# Thermocouple.net
KiCad netlist of a schematic drawn in EAGLE
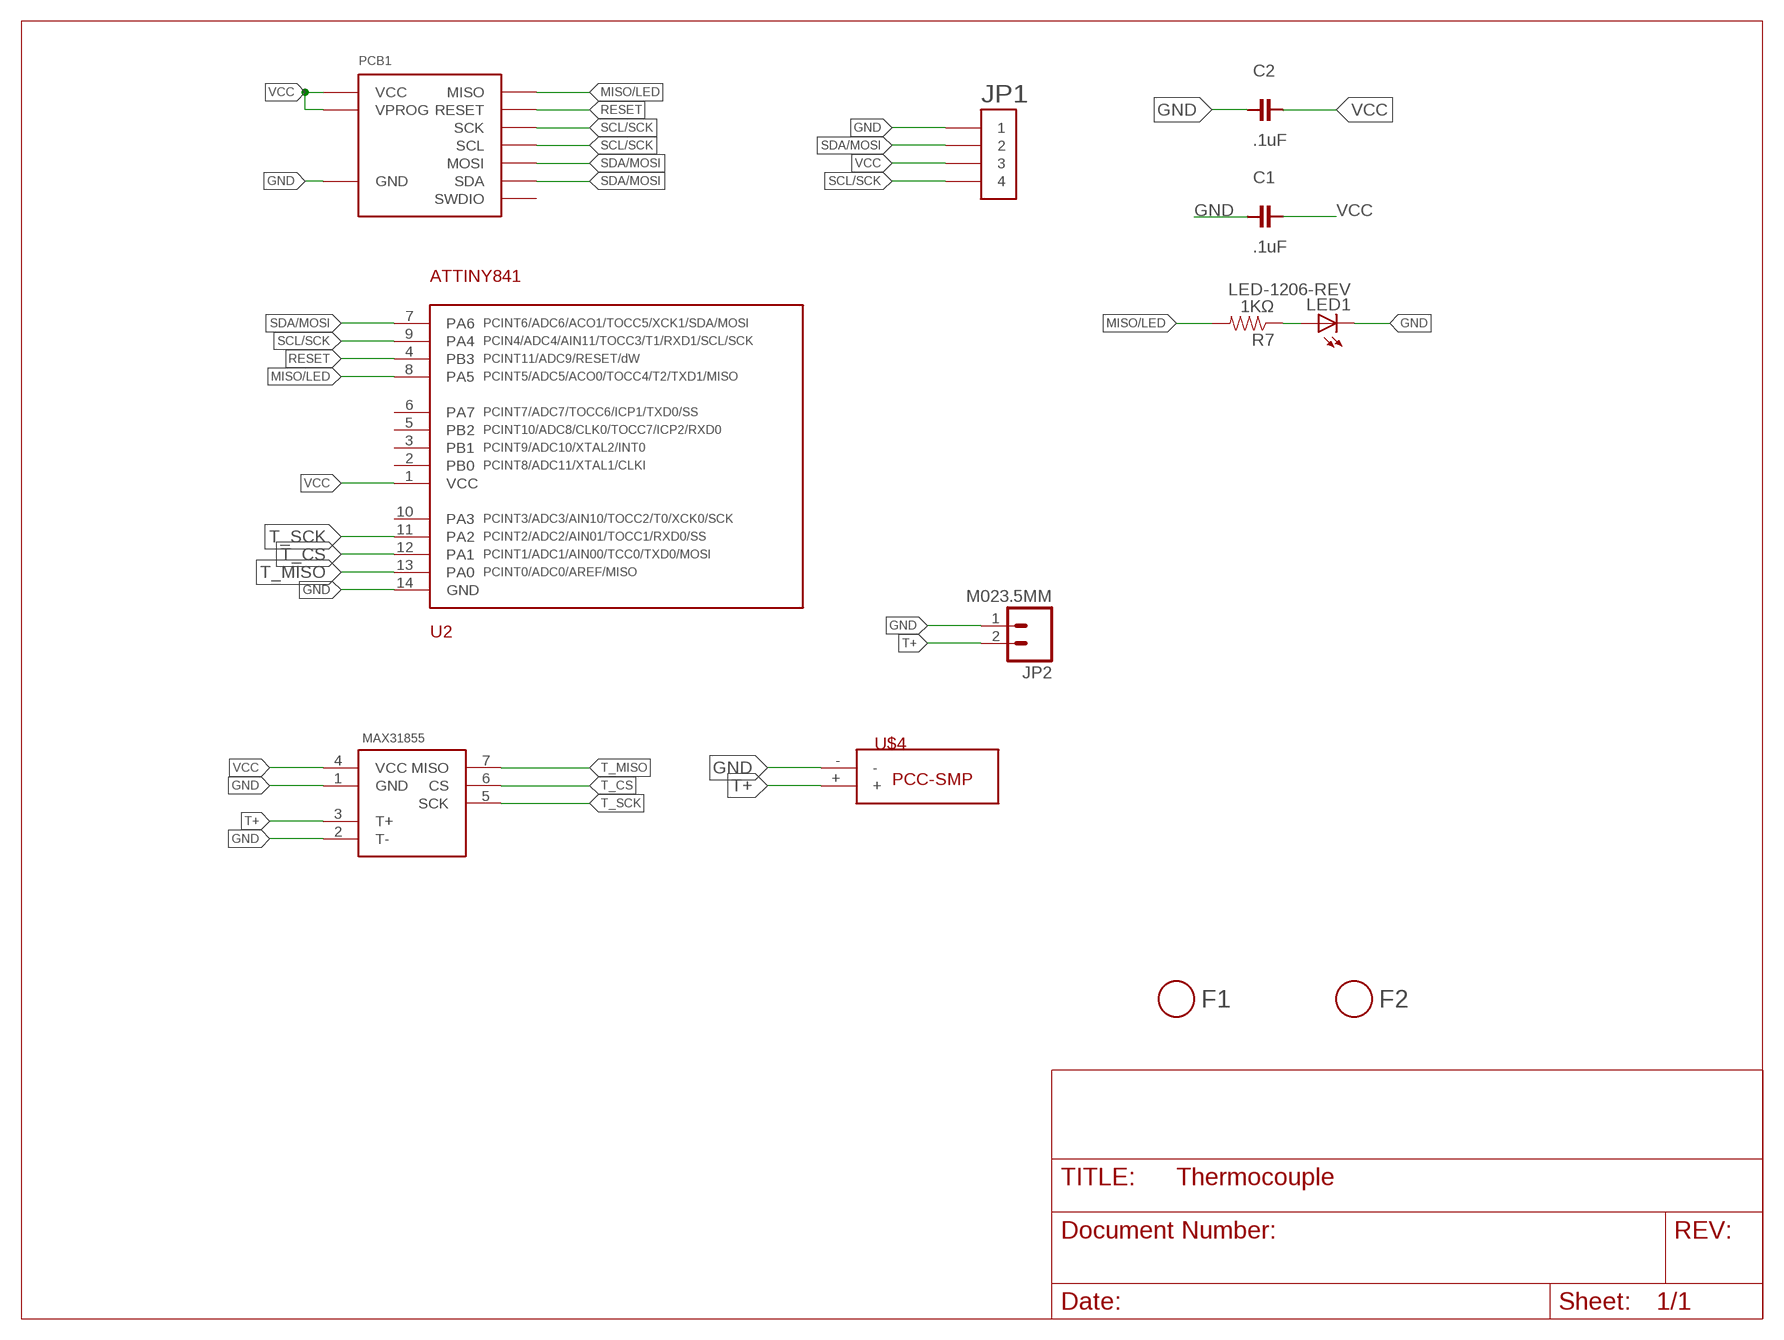
[diagram p0: schematic, sheet 1]

(export (version "E")
  (design (tool "Eeschema 10.0.6"))
  (components
    (comp (ref "C1")
      (value ".1uF")
      (footprint "eagle-import:0603")
      (fields (field (name "PARTNUM") "C0603C104K5RACTU"))
      (libsource (lib "eagle-import") (part "CAPACITOR-.1UF"))
    )
    (comp (ref "C2")
      (value ".1uF")
      (footprint "eagle-import:0603")
      (fields (field (name "PARTNUM") "C0603C104K5RACTU"))
      (libsource (lib "eagle-import") (part "CAPACITOR-.1UF"))
    )
    (comp (ref "F1")
      (value "FIDUCIAL")
      (footprint "eagle-import:FIDUCIAL_1MM")
      (libsource (lib "eagle-import") (part "FIDUCIAL"))
    )
    (comp (ref "F2")
      (value "FIDUCIAL")
      (footprint "eagle-import:FIDUCIAL_1MM")
      (libsource (lib "eagle-import") (part "FIDUCIAL"))
    )
    (comp (ref "JP1")
      (value "HEADER-1X4-AMPMODU")
      (footprint "eagle-import:AMPMODU-4P")
      (fields (field (name "PARTNUM") "147721-3"))
      (libsource (lib "eagle-import") (part "HEADER-1X4-AMPMODU"))
    )
    (comp (ref "JP2")
      (value "M023.5MM")
      (footprint "eagle-import:SCREWTERMINAL-3.5MM-2")
      (libsource (lib "eagle-import") (part "M023.5MM"))
    )
    (comp (ref "LED1")
      (value "LED-1206-REV")
      (footprint "eagle-import:LED-1206-REV")
      (fields (field (name "PARTNUM") "LTST-C230TBKT"))
      (libsource (lib "eagle-import") (part "LED-1206-REV"))
    )
    (comp (ref "PCB1")
      (value "DEVICE-PCB")
      (footprint "eagle-import:DEVICE-PCB")
      (fields (field (name "PARTNUM") "Therm PCB"))
      (libsource (lib "eagle-import") (part "DEVICE-PCB"))
    )
    (comp (ref "R7")
      (value "1KΩ")
      (footprint "eagle-import:0603")
      (fields (field (name "PARTNUM") "ERJ-3EKF1001V"))
      (libsource (lib "eagle-import") (part "RESISTOR-1KΩ"))
    )
    (comp (ref "U$4")
      (value "PCC-SMP")
      (footprint "eagle-import:PCC-SMP")
      (libsource (lib "eagle-import") (part "PCC-SMP"))
    )
    (comp (ref "U$5")
      (value "MAX31855")
      (footprint "eagle-import:SOIC-8")
      (libsource (lib "eagle-import") (part "MAX31855"))
    )
    (comp (ref "U2")
      (value "ATTINY841")
      (footprint "eagle-import:SOIC-14")
      (fields (field (name "PARTNUM") "ATTINY841-SSUR"))
      (libsource (lib "eagle-import") (part "ATTINY841"))
    )
  )
  (nets
    (net (code "1") (name "GND") (class "Default")
      (node (ref "C1") (pin "2") (pinfunction "2_2") (pintype "passive"))
      (node (ref "C2") (pin "2") (pinfunction "2_2") (pintype "passive"))
      (node (ref "JP1") (pin "P$1") (pinfunction "1_P$1") (pintype "bidirectional"))
      (node (ref "JP1") (pin "P$2") (pinfunction "1_P$2") (pintype "bidirectional"))
      (node (ref "JP2") (pin "1") (pinfunction "1_1") (pintype "passive"))
      (node (ref "LED1") (pin "C") (pinfunction "C_C") (pintype "passive"))
      (node (ref "PCB1") (pin "GND") (pinfunction "GND_GND") (pintype "bidirectional"))
      (node (ref "U$4") (pin "-") (pinfunction "-_-") (pintype "bidirectional"))
      (node (ref "U$5") (pin "1") (pinfunction "GND_1") (pintype "bidirectional"))
      (node (ref "U$5") (pin "2") (pinfunction "T-_2") (pintype "bidirectional"))
      (node (ref "U2") (pin "14") (pinfunction "GND_14") (pintype "bidirectional"))
    )
    (net (code "2") (name "MISO{slash}LED") (class "Default")
      (node (ref "PCB1") (pin "MISO") (pinfunction "MISO_MISO") (pintype "bidirectional"))
      (node (ref "R7") (pin "2") (pinfunction "2_2") (pintype "passive"))
      (node (ref "U2") (pin "8") (pinfunction "PA5_8") (pintype "bidirectional"))
    )
    (net (code "3") (name "Net-(LED1-PadA)") (class "Default")
      (node (ref "LED1") (pin "A") (pinfunction "A_A") (pintype "passive"))
      (node (ref "R7") (pin "1") (pinfunction "1_1") (pintype "passive"))
    )
    (net (code "4") (name "RESET") (class "Default")
      (node (ref "PCB1") (pin "RESET") (pinfunction "RESET_RESET") (pintype "bidirectional"))
      (node (ref "U2") (pin "4") (pinfunction "PB3_4") (pintype "bidirectional"))
    )
    (net (code "5") (name "SCL{slash}SCK") (class "Default")
      (node (ref "JP1") (pin "P$7") (pinfunction "4_P$7") (pintype "bidirectional"))
      (node (ref "JP1") (pin "P$8") (pinfunction "4_P$8") (pintype "bidirectional"))
      (node (ref "PCB1") (pin "CLK") (pinfunction "SCK_CLK") (pintype "bidirectional"))
      (node (ref "PCB1") (pin "SCL") (pinfunction "SCL_SCL") (pintype "bidirectional"))
      (node (ref "U2") (pin "9") (pinfunction "PA4_9") (pintype "bidirectional"))
    )
    (net (code "6") (name "SDA{slash}MOSI") (class "Default")
      (node (ref "JP1") (pin "P$3") (pinfunction "2_P$3") (pintype "bidirectional"))
      (node (ref "JP1") (pin "P$4") (pinfunction "2_P$4") (pintype "bidirectional"))
      (node (ref "PCB1") (pin "MOSI") (pinfunction "MOSI_MOSI") (pintype "bidirectional"))
      (node (ref "PCB1") (pin "SDA") (pinfunction "SDA_SDA") (pintype "bidirectional"))
      (node (ref "U2") (pin "7") (pinfunction "PA6_7") (pintype "bidirectional"))
    )
    (net (code "7") (name "T+") (class "Default")
      (node (ref "JP2") (pin "2") (pinfunction "2_2") (pintype "passive"))
      (node (ref "U$4") (pin "+") (pinfunction "+_+") (pintype "bidirectional"))
      (node (ref "U$5") (pin "3") (pinfunction "T+_3") (pintype "bidirectional"))
    )
    (net (code "8") (name "T_CS") (class "Default")
      (node (ref "U$5") (pin "6") (pinfunction "CS_6") (pintype "bidirectional"))
      (node (ref "U2") (pin "12") (pinfunction "PA1_12") (pintype "bidirectional"))
    )
    (net (code "9") (name "T_MISO") (class "Default")
      (node (ref "U$5") (pin "7") (pinfunction "MISO_7") (pintype "bidirectional"))
      (node (ref "U2") (pin "13") (pinfunction "PA0_13") (pintype "bidirectional"))
    )
    (net (code "10") (name "T_SCK") (class "Default")
      (node (ref "U$5") (pin "5") (pinfunction "SCK_5") (pintype "bidirectional"))
      (node (ref "U2") (pin "11") (pinfunction "PA2_11") (pintype "bidirectional"))
    )
    (net (code "11") (name "VCC") (class "Default")
      (node (ref "C1") (pin "1") (pinfunction "1_1") (pintype "passive"))
      (node (ref "C2") (pin "1") (pinfunction "1_1") (pintype "passive"))
      (node (ref "JP1") (pin "P$5") (pinfunction "3_P$5") (pintype "bidirectional"))
      (node (ref "JP1") (pin "P$6") (pinfunction "3_P$6") (pintype "bidirectional"))
      (node (ref "PCB1") (pin "VCC") (pinfunction "VCC_VCC") (pintype "bidirectional"))
      (node (ref "PCB1") (pin "VPROG") (pinfunction "VPROG_VPROG") (pintype "bidirectional"))
      (node (ref "U$5") (pin "4") (pinfunction "VCC_4") (pintype "bidirectional"))
      (node (ref "U2") (pin "1") (pinfunction "VCC_1") (pintype "bidirectional"))
    )
    (net (code "12") (name "unconnected-(PCB1-PadSWDIO)") (class "Default")
      (node (ref "PCB1") (pin "SWDIO") (pinfunction "SWDIO_SWDIO") (pintype "bidirectional"))
    )
    (net (code "13") (name "unconnected-(U2-PA3-Pad10)") (class "Default")
      (node (ref "U2") (pin "10") (pinfunction "PA3_10") (pintype "bidirectional"))
    )
    (net (code "14") (name "unconnected-(U2-PA7-Pad6)") (class "Default")
      (node (ref "U2") (pin "6") (pinfunction "PA7_6") (pintype "bidirectional"))
    )
    (net (code "15") (name "unconnected-(U2-PB0-Pad2)") (class "Default")
      (node (ref "U2") (pin "2") (pinfunction "PB0_2") (pintype "bidirectional"))
    )
    (net (code "16") (name "unconnected-(U2-PB1-Pad3)") (class "Default")
      (node (ref "U2") (pin "3") (pinfunction "PB1_3") (pintype "bidirectional"))
    )
    (net (code "17") (name "unconnected-(U2-PB2-Pad5)") (class "Default")
      (node (ref "U2") (pin "5") (pinfunction "PB2_5") (pintype "bidirectional"))
    )
  )
)
